# estop_v2.net
KiCad netlist of a schematic drawn in EAGLE
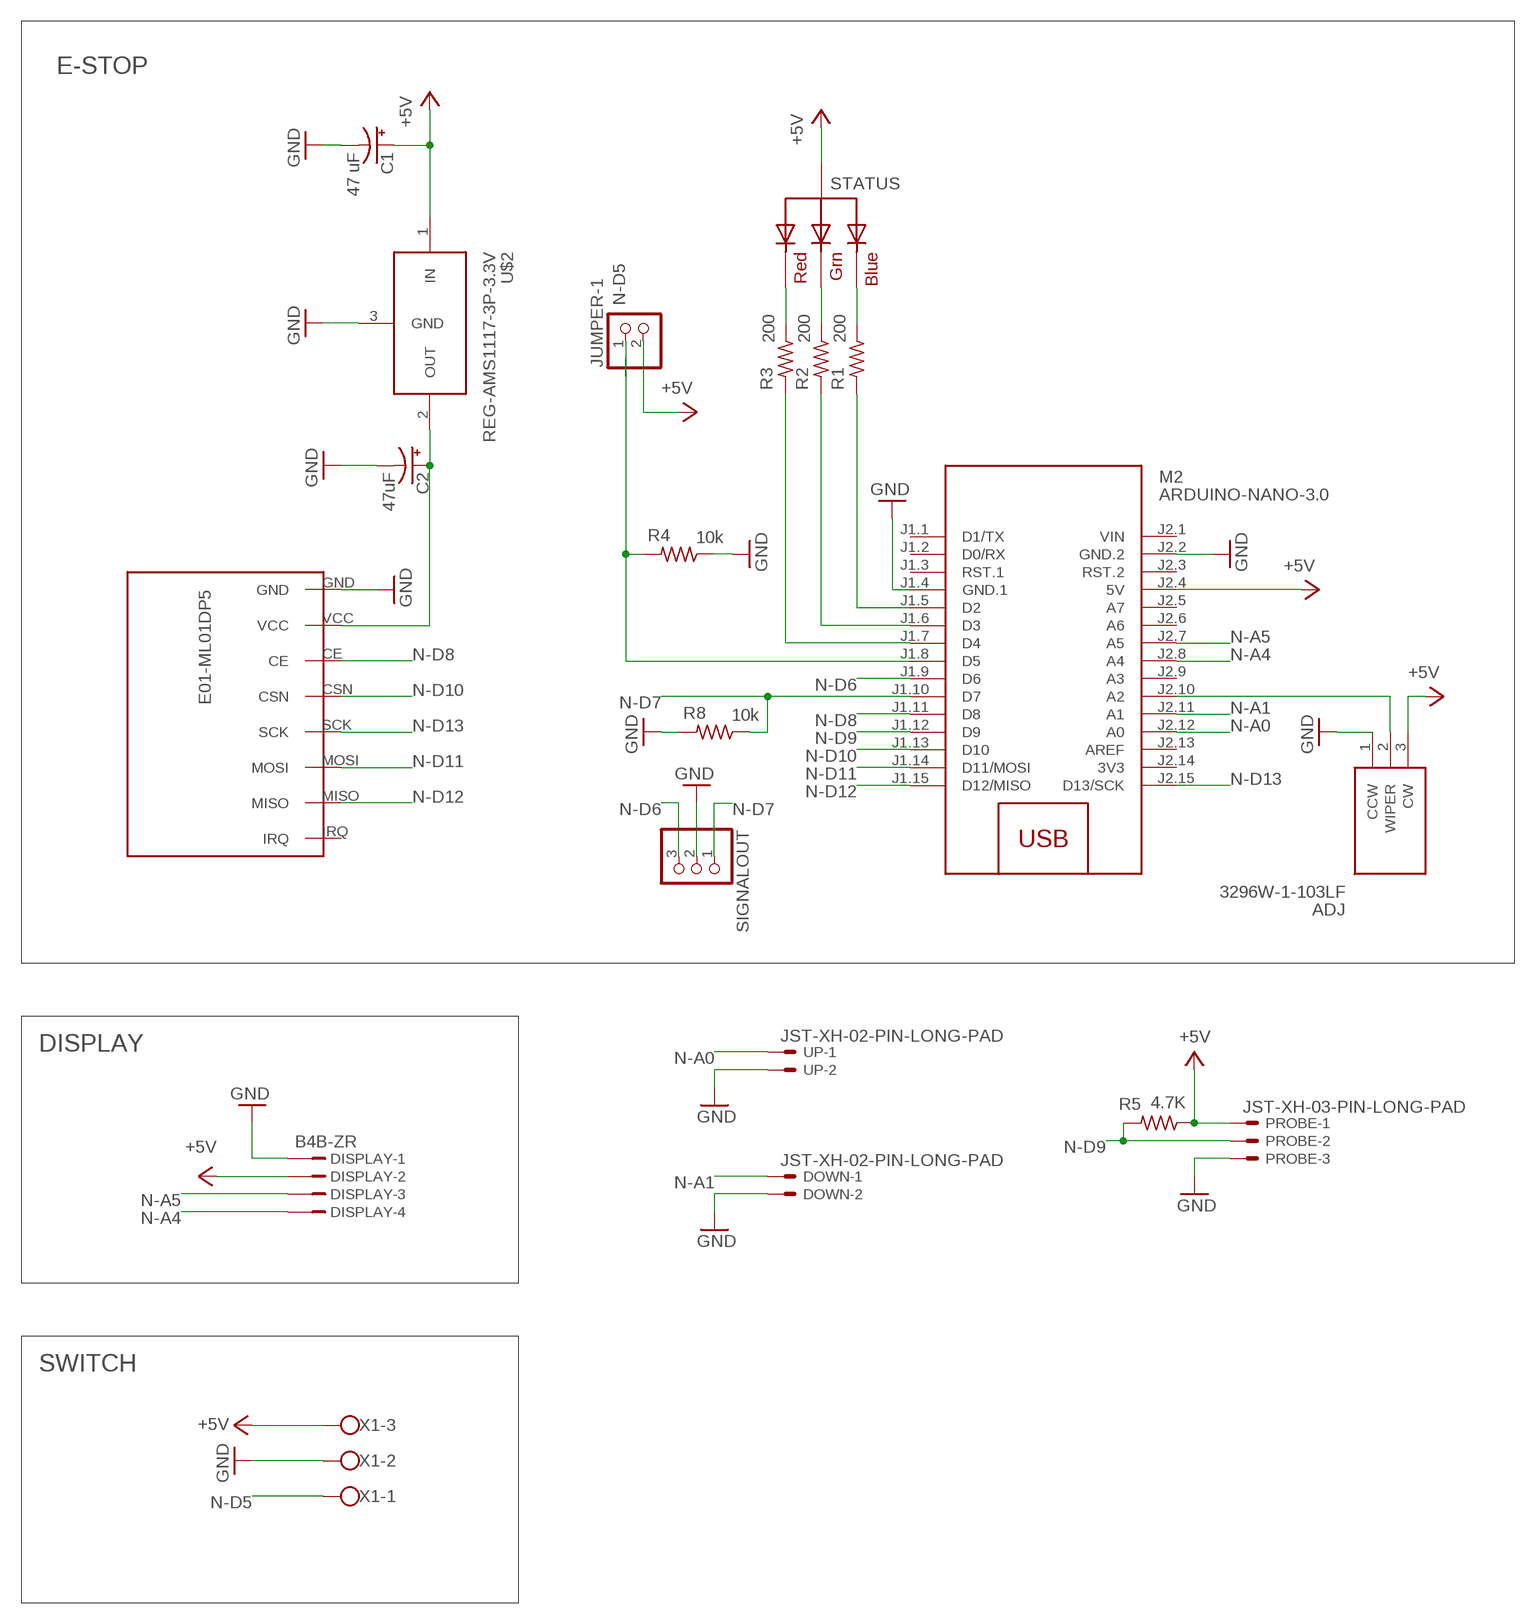
[diagram p0: schematic, sheet 1]

(export (version "E")
  (design (tool "Eeschema 10.0.6"))
  (components
    (comp (ref "ADJ")
      (value "3296W-1-103LF")
      (footprint "eagle-import:SHDR3W54P0X254_1X3_953X483X115")
      (fields (field (name "MOUSER_PART_NUMBER") "652-3296W-1-103LF"))
      (libsource (lib "eagle-import") (part "3296W-1-103LF"))
    )
    (comp (ref "C1")
      (value "47 uF")
      (footprint "eagle-import:E2,5-5")
      (libsource (lib "eagle-import") (part "CPOL-USE2.5-5"))
    )
    (comp (ref "C2")
      (value "47uF")
      (footprint "eagle-import:E2,5-5")
      (libsource (lib "eagle-import") (part "CPOL-USE2.5-5"))
    )
    (comp (ref "DISPLAY")
      (value "B4B-ZR")
      (footprint "eagle-import:B4B-ZR")
      (fields (field (name "MF") "FARNELL") (field (name "MPN") "B4B-ZR(LF)(SN)"))
      (libsource (lib "eagle-import") (part "?4B-ZRB"))
    )
    (comp (ref "DOWN")
      (value "JST-XH-02-PIN-LONG-PAD")
      (footprint "eagle-import:JST-XH-02-PACKAGE-LONG-PAD")
      (libsource (lib "eagle-import") (part "JST-XH-02-PIN-LONG-PAD"))
    )
    (comp (ref "JUMPER-1")
      (value "PINHD-1X2")
      (footprint "eagle-import:1X02")
      (libsource (lib "eagle-import") (part "PINHD-1X2"))
    )
    (comp (ref "M2")
      (value "ARDUINO-NANO-3.0")
      (footprint "eagle-import:ARDUINO-NANO-3.0")
      (libsource (lib "eagle-import") (part "ARDUINO-NANO-3.0"))
    )
    (comp (ref "PROBE")
      (value "JST-XH-03-PIN-LONG-PAD")
      (footprint "eagle-import:JST-XH-03-PACKAGE-LONG-PAD")
      (libsource (lib "eagle-import") (part "JST-XH-03-PIN-LONG-PAD"))
    )
    (comp (ref "R1")
      (value "200")
      (footprint "eagle-import:M0805")
      (libsource (lib "eagle-import") (part "R-US_M0805"))
    )
    (comp (ref "R2")
      (value "200")
      (footprint "eagle-import:M0805")
      (libsource (lib "eagle-import") (part "R-US_M0805"))
    )
    (comp (ref "R3")
      (value "200")
      (footprint "eagle-import:M0805")
      (libsource (lib "eagle-import") (part "R-US_M0805"))
    )
    (comp (ref "R4")
      (value "10k")
      (footprint "eagle-import:M0805")
      (libsource (lib "eagle-import") (part "R-US_M0805"))
    )
    (comp (ref "R5")
      (value "4.7K")
      (footprint "eagle-import:M0805")
      (libsource (lib "eagle-import") (part "R-US_M0805"))
    )
    (comp (ref "R8")
      (value "10k")
      (footprint "eagle-import:M0805")
      (libsource (lib "eagle-import") (part "R-US_M0805"))
    )
    (comp (ref "SIGNALOUT")
      (value "PINHD-1X3")
      (footprint "eagle-import:1X03")
      (libsource (lib "eagle-import") (part "PINHD-1X3"))
    )
    (comp (ref "STATUS")
      (value "RGBLED_CA-5MM")
      (footprint "eagle-import:LED5MMRGB")
      (libsource (lib "eagle-import") (part "RGBLED_CA-5MM"))
    )
    (comp (ref "U$1")
      (value "E01-ML01DP5")
      (footprint "eagle-import:E01-ML01DP5")
      (libsource (lib "eagle-import") (part "E01-ML01DP5"))
    )
    (comp (ref "U$2")
      (value "REG-AMS1117-3P-3.3V")
      (footprint "eagle-import:REG-AMS1117-3P")
      (libsource (lib "eagle-import") (part "REG-AMS1117-3P-3.3V"))
    )
    (comp (ref "UP")
      (value "JST-XH-02-PIN-LONG-PAD")
      (footprint "eagle-import:JST-XH-02-PACKAGE-LONG-PAD")
      (libsource (lib "eagle-import") (part "JST-XH-02-PIN-LONG-PAD"))
    )
    (comp (ref "X1")
      (value "W237-103")
      (footprint "eagle-import:W237-103")
      (fields (field (name "MPN") "237-103"))
      (libsource (lib "eagle-import") (part "W237-103"))
    )
  )
  (nets
    (net (code "1") (name "+5V") (class "Default")
      (node (ref "ADJ") (pin "3") (pinfunction "CW_3") (pintype "bidirectional"))
      (node (ref "C1") (pin "+") (pinfunction "+_+") (pintype "passive"))
      (node (ref "DISPLAY") (pin "2") (pinfunction "1_2") (pintype "passive"))
      (node (ref "JUMPER-1") (pin "2") (pinfunction "2_2") (pintype "passive"))
      (node (ref "M2") (pin "J2.4") (pinfunction "5V_J2.4") (pintype "power_in"))
      (node (ref "PROBE") (pin "1") (pinfunction "S_1") (pintype "passive"))
      (node (ref "R5") (pin "1") (pinfunction "1_1") (pintype "passive"))
      (node (ref "STATUS") (pin "2") (pinfunction "VCC_2") (pintype "bidirectional"))
      (node (ref "U$2") (pin "1") (pinfunction "IN_1") (pintype "bidirectional"))
      (node (ref "X1") (pin "3") (pinfunction "KL_3") (pintype "passive"))
    )
    (net (code "2") (name "/3V3") (class "Default")
      (node (ref "M2") (pin "J2.14") (pinfunction "3V3_J2.14") (pintype "power_in"))
    )
    (net (code "3") (name "/N-A0") (class "Default")
      (node (ref "M2") (pin "J2.12") (pinfunction "A0_J2.12") (pintype "bidirectional"))
      (node (ref "UP") (pin "1") (pinfunction "S_1") (pintype "passive"))
    )
    (net (code "4") (name "/N-A1") (class "Default")
      (node (ref "DOWN") (pin "1") (pinfunction "S_1") (pintype "passive"))
      (node (ref "M2") (pin "J2.11") (pinfunction "A1_J2.11") (pintype "bidirectional"))
    )
    (net (code "5") (name "/N-A4") (class "Default")
      (node (ref "DISPLAY") (pin "4") (pinfunction "1_4") (pintype "passive"))
      (node (ref "M2") (pin "J2.8") (pinfunction "A4_J2.8") (pintype "bidirectional"))
    )
    (net (code "6") (name "/N-A5") (class "Default")
      (node (ref "DISPLAY") (pin "3") (pinfunction "1_3") (pintype "passive"))
      (node (ref "M2") (pin "J2.7") (pinfunction "A5_J2.7") (pintype "bidirectional"))
    )
    (net (code "7") (name "/N-D5") (class "Default")
      (node (ref "JUMPER-1") (pin "1") (pinfunction "1_1") (pintype "passive"))
      (node (ref "M2") (pin "J1.8") (pinfunction "D5_J1.8") (pintype "bidirectional"))
      (node (ref "R4") (pin "2") (pinfunction "2_2") (pintype "passive"))
      (node (ref "X1") (pin "1") (pinfunction "KL_1") (pintype "passive"))
    )
    (net (code "8") (name "/N-D6") (class "Default")
      (node (ref "M2") (pin "J1.9") (pinfunction "D6_J1.9") (pintype "bidirectional"))
      (node (ref "SIGNALOUT") (pin "3") (pinfunction "3_3") (pintype "passive"))
    )
    (net (code "9") (name "/N-D7") (class "Default")
      (node (ref "M2") (pin "J1.10") (pinfunction "D7_J1.10") (pintype "bidirectional"))
      (node (ref "R8") (pin "1") (pinfunction "1_1") (pintype "passive"))
      (node (ref "SIGNALOUT") (pin "1") (pinfunction "1_1") (pintype "passive"))
    )
    (net (code "10") (name "/N-D8") (class "Default")
      (node (ref "M2") (pin "J1.11") (pinfunction "D8_J1.11") (pintype "bidirectional"))
      (node (ref "U$1") (pin "CE") (pinfunction "CE_CE") (pintype "bidirectional"))
    )
    (net (code "11") (name "/N-D9") (class "Default")
      (node (ref "M2") (pin "J1.12") (pinfunction "D9_J1.12") (pintype "bidirectional"))
      (node (ref "PROBE") (pin "2") (pinfunction "S_2") (pintype "passive"))
      (node (ref "R5") (pin "2") (pinfunction "2_2") (pintype "passive"))
    )
    (net (code "12") (name "/N-D10") (class "Default")
      (node (ref "M2") (pin "J1.13") (pinfunction "D10_J1.13") (pintype "bidirectional"))
      (node (ref "U$1") (pin "CSN") (pinfunction "CSN_CSN") (pintype "bidirectional"))
    )
    (net (code "13") (name "/N-D11") (class "Default")
      (node (ref "M2") (pin "J1.14") (pinfunction "D11/MOSI_J1.14") (pintype "bidirectional"))
      (node (ref "U$1") (pin "MOSI") (pinfunction "MOSI_MOSI") (pintype "bidirectional"))
    )
    (net (code "14") (name "/N-D12") (class "Default")
      (node (ref "M2") (pin "J1.15") (pinfunction "D12/MISO_J1.15") (pintype "bidirectional"))
      (node (ref "U$1") (pin "MISO") (pinfunction "MISO_MISO") (pintype "bidirectional"))
    )
    (net (code "15") (name "/N-D13") (class "Default")
      (node (ref "M2") (pin "J2.15") (pinfunction "D13/SCK_J2.15") (pintype "bidirectional"))
      (node (ref "U$1") (pin "SCK") (pinfunction "SCK_SCK") (pintype "bidirectional"))
    )
    (net (code "16") (name "/VIN") (class "Default")
      (node (ref "M2") (pin "J2.1") (pinfunction "VIN_J2.1") (pintype "power_in"))
    )
    (net (code "17") (name "GND") (class "Default")
      (node (ref "ADJ") (pin "1") (pinfunction "CCW_1") (pintype "bidirectional"))
      (node (ref "C1") (pin "-") (pinfunction "-_-") (pintype "passive"))
      (node (ref "C2") (pin "-") (pinfunction "-_-") (pintype "passive"))
      (node (ref "DISPLAY") (pin "1") (pinfunction "1_1") (pintype "passive"))
      (node (ref "DOWN") (pin "2") (pinfunction "S_2") (pintype "passive"))
      (node (ref "M2") (pin "J1.4") (pinfunction "GND.1_J1.4") (pintype "power_in"))
      (node (ref "M2") (pin "J2.2") (pinfunction "GND.2_J2.2") (pintype "power_in"))
      (node (ref "PROBE") (pin "3") (pinfunction "S_3") (pintype "passive"))
      (node (ref "R4") (pin "1") (pinfunction "1_1") (pintype "passive"))
      (node (ref "R8") (pin "2") (pinfunction "2_2") (pintype "passive"))
      (node (ref "SIGNALOUT") (pin "2") (pinfunction "2_2") (pintype "passive"))
      (node (ref "U$1") (pin "GND") (pinfunction "GND_GND") (pintype "bidirectional"))
      (node (ref "U$2") (pin "3") (pinfunction "GND_3") (pintype "bidirectional"))
      (node (ref "UP") (pin "2") (pinfunction "S_2") (pintype "passive"))
      (node (ref "X1") (pin "2") (pinfunction "KL_2") (pintype "passive"))
    )
    (net (code "18") (name "Net-(ADJ-WIPER)") (class "Default")
      (node (ref "ADJ") (pin "2") (pinfunction "WIPER_2") (pintype "bidirectional"))
      (node (ref "M2") (pin "J2.10") (pinfunction "A2_J2.10") (pintype "bidirectional"))
    )
    (net (code "19") (name "Net-(M2-D2)") (class "Default")
      (node (ref "M2") (pin "J1.5") (pinfunction "D2_J1.5") (pintype "bidirectional"))
      (node (ref "R1") (pin "2") (pinfunction "2_2") (pintype "passive"))
    )
    (net (code "20") (name "Net-(M2-D3)") (class "Default")
      (node (ref "M2") (pin "J1.6") (pinfunction "D3_J1.6") (pintype "bidirectional"))
      (node (ref "R2") (pin "2") (pinfunction "2_2") (pintype "passive"))
    )
    (net (code "21") (name "Net-(M2-D4)") (class "Default")
      (node (ref "M2") (pin "J1.7") (pinfunction "D4_J1.7") (pintype "bidirectional"))
      (node (ref "R3") (pin "2") (pinfunction "2_2") (pintype "passive"))
    )
    (net (code "22") (name "Net-(STATUS-BLUE)") (class "Default")
      (node (ref "R1") (pin "1") (pinfunction "1_1") (pintype "passive"))
      (node (ref "STATUS") (pin "4") (pinfunction "BLUE_4") (pintype "bidirectional"))
    )
    (net (code "23") (name "Net-(STATUS-GREEN)") (class "Default")
      (node (ref "R2") (pin "1") (pinfunction "1_1") (pintype "passive"))
      (node (ref "STATUS") (pin "3") (pinfunction "GREEN_3") (pintype "bidirectional"))
    )
    (net (code "24") (name "Net-(STATUS-RED)") (class "Default")
      (node (ref "R3") (pin "1") (pinfunction "1_1") (pintype "passive"))
      (node (ref "STATUS") (pin "1") (pinfunction "RED_1") (pintype "bidirectional"))
    )
    (net (code "25") (name "Net-(U$2-OUT)") (class "Default")
      (node (ref "C2") (pin "+") (pinfunction "+_+") (pintype "passive"))
      (node (ref "U$1") (pin "VCC") (pinfunction "VCC_VCC") (pintype "bidirectional"))
      (node (ref "U$2") (pin "2") (pinfunction "OUT_2") (pintype "bidirectional"))
    )
    (net (code "26") (name "unconnected-(M2-A3-PadJ2.9)") (class "Default")
      (node (ref "M2") (pin "J2.9") (pinfunction "A3_J2.9") (pintype "bidirectional"))
    )
    (net (code "27") (name "unconnected-(M2-A6-PadJ2.6)") (class "Default")
      (node (ref "M2") (pin "J2.6") (pinfunction "A6_J2.6") (pintype "bidirectional"))
    )
    (net (code "28") (name "unconnected-(M2-A7-PadJ2.5)") (class "Default")
      (node (ref "M2") (pin "J2.5") (pinfunction "A7_J2.5") (pintype "bidirectional"))
    )
    (net (code "29") (name "unconnected-(M2-AREF-PadJ2.13)") (class "Default")
      (node (ref "M2") (pin "J2.13") (pinfunction "AREF_J2.13") (pintype "bidirectional"))
    )
    (net (code "30") (name "unconnected-(M2-D0{slash}RX-PadJ1.2)") (class "Default")
      (node (ref "M2") (pin "J1.2") (pinfunction "D0/RX_J1.2") (pintype "bidirectional"))
    )
    (net (code "31") (name "unconnected-(M2-D1{slash}TX-PadJ1.1)") (class "Default")
      (node (ref "M2") (pin "J1.1") (pinfunction "D1/TX_J1.1") (pintype "bidirectional"))
    )
    (net (code "32") (name "unconnected-(M2-RST.1-PadJ1.3)") (class "Default")
      (node (ref "M2") (pin "J1.3") (pinfunction "RST.1_J1.3") (pintype "bidirectional"))
    )
    (net (code "33") (name "unconnected-(M2-RST.2-PadJ2.3)") (class "Default")
      (node (ref "M2") (pin "J2.3") (pinfunction "RST.2_J2.3") (pintype "bidirectional"))
    )
    (net (code "34") (name "unconnected-(U$1-PadIRQ)") (class "Default")
      (node (ref "U$1") (pin "IRQ") (pinfunction "IRQ_IRQ") (pintype "bidirectional"))
    )
  )
)
